# MINIBLDC.net
KiCad netlist of a schematic drawn in Altium Designer
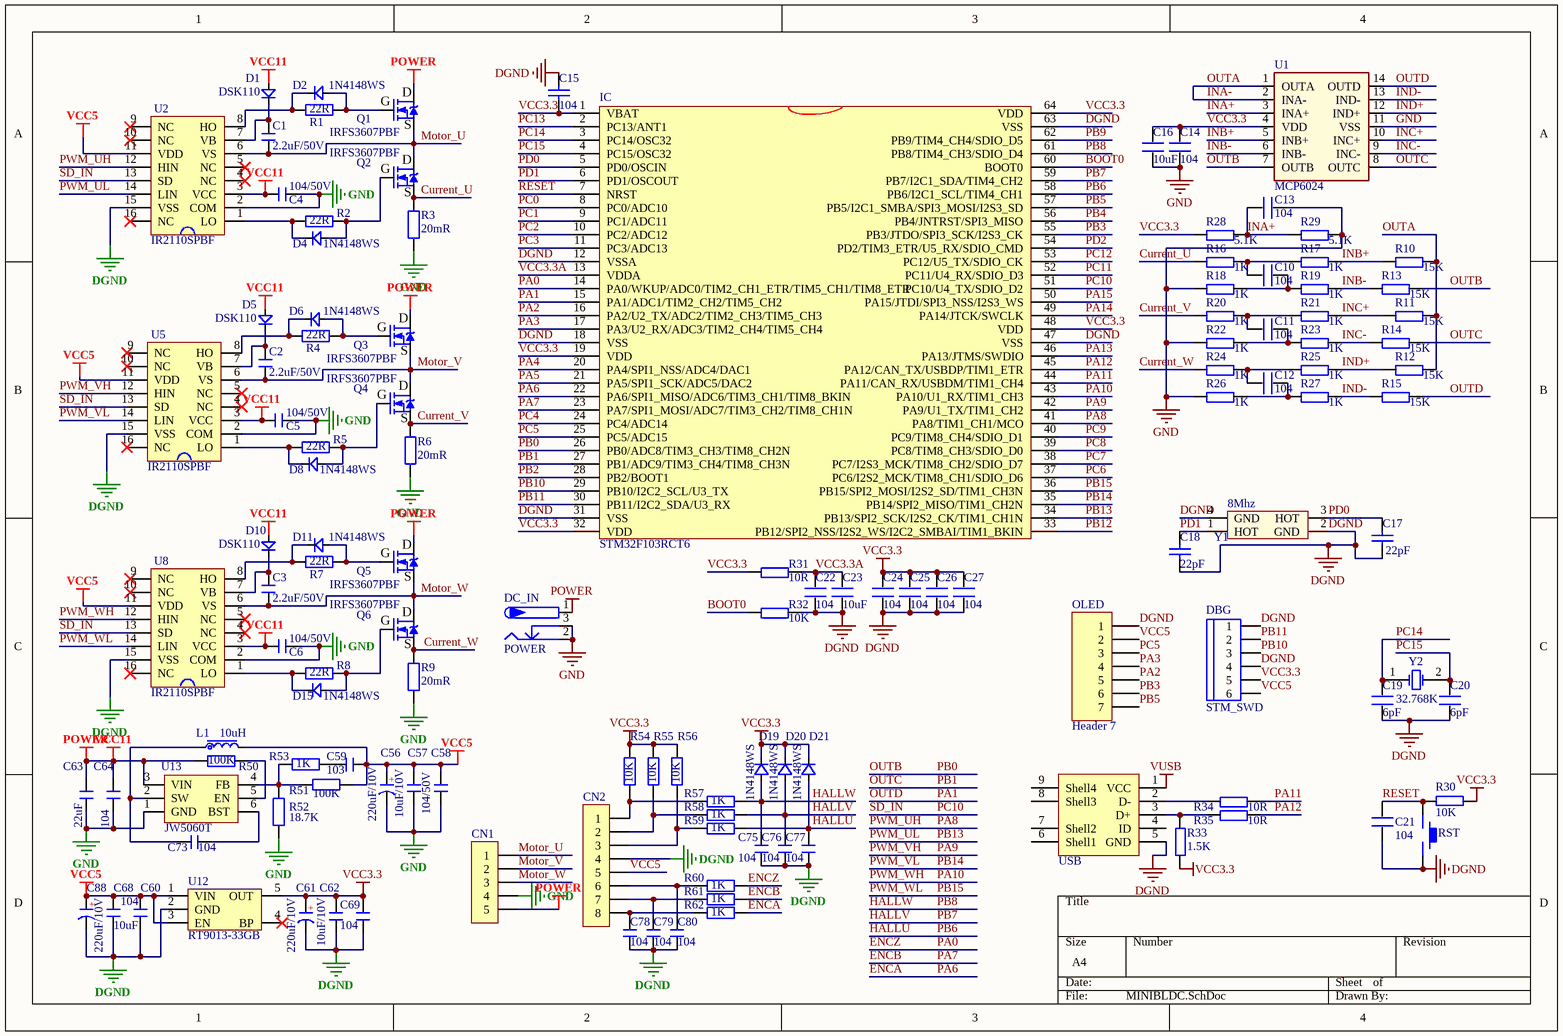
[diagram p0: MINIBLDC.SchDoc]

(export (version "E")
  (design (tool "Eeschema 10.0.6"))
  (components
    (comp (ref "C1")
      (value "2.2uF/50V")
      (footprint "C 0603")
      (description "无极性贴片电容")
      (fields (field (name "版权归属") "源创客"))
      (libsource (lib "电阻-电容-电感") (part "C"))
    )
    (comp (ref "C2")
      (value "2.2uF/50V")
      (footprint "C 0603")
      (description "无极性贴片电容")
      (fields (field (name "版权归属") "源创客"))
      (libsource (lib "电阻-电容-电感") (part "C"))
    )
    (comp (ref "C3")
      (value "2.2uF/50V")
      (footprint "C 0603")
      (description "无极性贴片电容")
      (fields (field (name "版权归属") "源创客"))
      (libsource (lib "电阻-电容-电感") (part "C"))
    )
    (comp (ref "C4")
      (value "104/50V")
      (footprint "C 0603")
      (description "无极性贴片电容")
      (fields (field (name "版权归属") "源创客"))
      (libsource (lib "电阻-电容-电感") (part "C"))
    )
    (comp (ref "C5")
      (value "104/50V")
      (footprint "C 0603")
      (description "无极性贴片电容")
      (fields (field (name "版权归属") "源创客"))
      (libsource (lib "电阻-电容-电感") (part "C"))
    )
    (comp (ref "C6")
      (value "104/50V")
      (footprint "C 0603")
      (description "无极性贴片电容")
      (fields (field (name "版权归属") "源创客"))
      (libsource (lib "电阻-电容-电感") (part "C"))
    )
    (comp (ref "C10") (value "104") (footprint "C 0603") (libsource (lib "IMX6UL_ALPHA(底板)_V2.0") (part "C")))
    (comp (ref "C11") (value "104") (footprint "C 0603") (libsource (lib "IMX6UL_ALPHA(底板)_V2.0") (part "C")))
    (comp (ref "C12") (value "104") (footprint "C 0603") (libsource (lib "IMX6UL_ALPHA(底板)_V2.0") (part "C")))
    (comp (ref "C13") (value "104") (footprint "C 0603") (libsource (lib "IMX6UL_ALPHA(底板)_V2.0") (part "C")))
    (comp (ref "C14") (value "104") (footprint "C 0603") (libsource (lib "IMX6UL_ALPHA(底板)_V2.0") (part "C")))
    (comp (ref "C15") (value "104") (footprint "C 0603") (libsource (lib "L476") (part "CAP")))
    (comp (ref "C16")
      (value "10uF")
      (footprint "C 0603")
      (libsource (lib "IMX6UL_ALPHA(底板)_V2.0") (part "C"))
    )
    (comp (ref "C17") (value "22pF") (footprint "C 0603") (libsource (lib "L476") (part "CAP")))
    (comp (ref "C18") (value "22pF") (footprint "C 0603") (libsource (lib "L476") (part "CAP")))
    (comp (ref "C19")
      (value "6pF")
      (footprint "C 0603")
      (libsource (lib "WarShip V3 STM32103封装库") (part "C"))
    )
    (comp (ref "C20")
      (value "6pF")
      (footprint "C 0603")
      (libsource (lib "WarShip V3 STM32103封装库") (part "C"))
    )
    (comp (ref "C21")
      (value "104")
      (footprint "C 0603")
      (libsource (lib "WarShip V3 STM32103封装库") (part "C"))
    )
    (comp (ref "C22")
      (value "104")
      (footprint "C 0603")
      (libsource (lib "WarShip V3 STM32103封装库") (part "C"))
    )
    (comp (ref "C23")
      (value "10uF")
      (footprint "C 0603")
      (libsource (lib "WarShip V3 STM32103封装库") (part "C"))
    )
    (comp (ref "C24")
      (value "104")
      (footprint "C 0603")
      (libsource (lib "WarShip V3 STM32103封装库") (part "C"))
    )
    (comp (ref "C25")
      (value "104")
      (footprint "C 0603")
      (libsource (lib "WarShip V3 STM32103封装库") (part "C"))
    )
    (comp (ref "C26")
      (value "104")
      (footprint "C 0603")
      (libsource (lib "WarShip V3 STM32103封装库") (part "C"))
    )
    (comp (ref "C27")
      (value "104")
      (footprint "C 0603")
      (libsource (lib "WarShip V3 STM32103封装库") (part "C"))
    )
    (comp (ref "C56")
      (value "220uF/10V")
      (footprint "CM D(6.3*5.4)")
      (description "贴片电解电容")
      (fields (field (name "版权归属") "源创客"))
      (libsource (lib "电阻-电容-电感") (part "C-CM"))
    )
    (comp (ref "C57")
      (value "10uF/10V")
      (footprint "C 0603")
      (description "无极性贴片电容")
      (fields (field (name "版权归属") "源创客"))
      (libsource (lib "电阻-电容-电感") (part "C"))
    )
    (comp (ref "C58")
      (value "104/50V")
      (footprint "C 0603")
      (description "无极性贴片电容")
      (fields (field (name "版权归属") "源创客"))
      (libsource (lib "电阻-电容-电感") (part "C"))
    )
    (comp (ref "C59")
      (value "103")
      (footprint "C 0603")
      (description "无极性贴片电容")
      (fields (field (name "版权归属") "源创客"))
      (libsource (lib "电阻-电容-电感") (part "C"))
    )
    (comp (ref "C60")
      (value "104")
      (footprint "C 0603")
      (description "无极性贴片电容")
      (fields (field (name "版权归属") "源创客"))
      (libsource (lib "电阻-电容-电感") (part "C"))
    )
    (comp (ref "C61")
      (value "220uF/10V")
      (footprint "CM D(6.3*5.4)")
      (description "贴片电解电容")
      (fields (field (name "版权归属") "源创客"))
      (libsource (lib "电阻-电容-电感") (part "C-CM"))
    )
    (comp (ref "C62")
      (value "10uF/10V")
      (footprint "C 0603")
      (description "无极性贴片电容")
      (fields (field (name "版权归属") "源创客"))
      (libsource (lib "电阻-电容-电感") (part "C"))
    )
    (comp (ref "C63")
      (value "22uF")
      (footprint "C 0805")
      (description "无极性贴片电容")
      (fields (field (name "版权归属") "源创客"))
      (libsource (lib "电阻-电容-电感") (part "C"))
    )
    (comp (ref "C64")
      (value "104")
      (footprint "C 0603")
      (description "无极性贴片电容")
      (fields (field (name "版权归属") "源创客"))
      (libsource (lib "电阻-电容-电感") (part "C"))
    )
    (comp (ref "C68")
      (value "10uF")
      (footprint "C 0603")
      (description "无极性贴片电容")
      (fields (field (name "版权归属") "源创客"))
      (libsource (lib "电阻-电容-电感") (part "C"))
    )
    (comp (ref "C69")
      (value "104")
      (footprint "C 0603")
      (description "无极性贴片电容")
      (fields (field (name "版权归属") "源创客"))
      (libsource (lib "电阻-电容-电感") (part "C"))
    )
    (comp (ref "C73")
      (value "104")
      (footprint "C 0603")
      (description "无极性贴片电容")
      (fields (field (name "版权归属") "源创客"))
      (libsource (lib "电阻-电容-电感") (part "C"))
    )
    (comp (ref "C75")
      (value "104")
      (footprint "C 0603")
      (description "无极性贴片电容")
      (fields (field (name "版权归属") "源创客"))
      (libsource (lib "电阻-电容-电感") (part "C"))
    )
    (comp (ref "C76")
      (value "104")
      (footprint "C 0603")
      (description "无极性贴片电容")
      (fields (field (name "版权归属") "源创客"))
      (libsource (lib "电阻-电容-电感") (part "C"))
    )
    (comp (ref "C77")
      (value "104")
      (footprint "C 0603")
      (description "无极性贴片电容")
      (fields (field (name "版权归属") "源创客"))
      (libsource (lib "电阻-电容-电感") (part "C"))
    )
    (comp (ref "C78")
      (value "104")
      (footprint "C 0603")
      (description "无极性贴片电容")
      (fields (field (name "版权归属") "源创客"))
      (libsource (lib "电阻-电容-电感") (part "C"))
    )
    (comp (ref "C79")
      (value "104")
      (footprint "C 0603")
      (description "无极性贴片电容")
      (fields (field (name "版权归属") "源创客"))
      (libsource (lib "电阻-电容-电感") (part "C"))
    )
    (comp (ref "C80")
      (value "104")
      (footprint "C 0603")
      (description "无极性贴片电容")
      (fields (field (name "版权归属") "源创客"))
      (libsource (lib "电阻-电容-电感") (part "C"))
    )
    (comp (ref "C88")
      (value "220uF/10V")
      (footprint "CM D(6.3*5.4)")
      (description "贴片电解电容")
      (fields (field (name "版权归属") "源创客"))
      (libsource (lib "电阻-电容-电感") (part "C-CM"))
    )
    (comp (ref "CN1")
      (value "HDR-1X5")
      (footprint "KF7620-5P")
      (description "5P接插件")
      (fields (field (name "版权归属") "源创客"))
      (libsource (lib "接插件") (part "Header 5"))
    )
    (comp (ref "CN2")
      (value "HDR-1X8")
      (footprint "HDR2.54-LI-8P")
      (description "8P接插件")
      (fields (field (name "版权归属") "源创客"))
      (libsource (lib "接插件") (part "Header 8"))
    )
    (comp (ref "D1")
      (value "DSK110")
      (footprint "SOD-123F")
      (description "通用二极管 100V-1A")
      (fields (field (name "版权归属") "源创客"))
      (libsource (lib "二极管-整流桥") (part "DSK110"))
    )
    (comp (ref "D2")
      (value "1N4148WS")
      (footprint "SOD-323")
      (description "通用二极管 700V-1A")
      (fields (field (name "版权归属") "源创客"))
      (libsource (lib "二极管-整流桥") (part "FR107"))
    )
    (comp (ref "D4")
      (value "1N4148WS")
      (footprint "SOD-323")
      (description "通用二极管 700V-1A")
      (fields (field (name "版权归属") "源创客"))
      (libsource (lib "二极管-整流桥") (part "FR107"))
    )
    (comp (ref "D5")
      (value "DSK110")
      (footprint "SOD-123F")
      (description "通用二极管 100V-1A")
      (fields (field (name "版权归属") "源创客"))
      (libsource (lib "二极管-整流桥") (part "DSK110"))
    )
    (comp (ref "D6")
      (value "1N4148WS")
      (footprint "SOD-323")
      (description "通用二极管 700V-1A")
      (fields (field (name "版权归属") "源创客"))
      (libsource (lib "二极管-整流桥") (part "FR107"))
    )
    (comp (ref "D8")
      (value "1N4148WS")
      (footprint "SOD-323")
      (description "通用二极管 700V-1A")
      (fields (field (name "版权归属") "源创客"))
      (libsource (lib "二极管-整流桥") (part "FR107"))
    )
    (comp (ref "D10")
      (value "DSK110")
      (footprint "SOD-123F")
      (description "通用二极管 100V-1A")
      (fields (field (name "版权归属") "源创客"))
      (libsource (lib "二极管-整流桥") (part "DSK110"))
    )
    (comp (ref "D11")
      (value "1N4148WS")
      (footprint "SOD-323")
      (description "通用二极管 700V-1A")
      (fields (field (name "版权归属") "源创客"))
      (libsource (lib "二极管-整流桥") (part "FR107"))
    )
    (comp (ref "D15")
      (value "1N4148WS")
      (footprint "SOD-323")
      (description "通用二极管 700V-1A")
      (fields (field (name "版权归属") "源创客"))
      (libsource (lib "二极管-整流桥") (part "FR107"))
    )
    (comp (ref "D19")
      (value "1N4148WS")
      (footprint "SOD-323")
      (description "通用二极管 1000V-1A")
      (fields (field (name "版权归属") "源创客"))
      (libsource (lib "二极管-整流桥") (part "RS1M"))
    )
    (comp (ref "D20")
      (value "1N4148WS")
      (footprint "SOD-323")
      (description "通用二极管 1000V-1A")
      (fields (field (name "版权归属") "源创客"))
      (libsource (lib "二极管-整流桥") (part "RS1M"))
    )
    (comp (ref "D21")
      (value "1N4148WS")
      (footprint "SOD-323")
      (description "通用二极管 1000V-1A")
      (fields (field (name "版权归属") "源创客"))
      (libsource (lib "二极管-整流桥") (part "RS1M"))
    )
    (comp (ref "DBG") (value "STM_SWD") (footprint "SH1.0-6P") (libsource (lib "MiniFly ") (part "HEAD6")))
    (comp (ref "DC_IN")
      (value "POWER")
      (footprint "DC10B")
      (description "低压电源接口")
      (fields (field (name "版权归属") "源创客"))
      (libsource (lib "IMX6UL_ALPHA(底板)_V2.0") (part "P-DC"))
    )
    (comp (ref "IC")
      (value "STM32F103RCT6")
      (footprint "LQFP64-10*10")
      (libsource (lib "MiniSTM32 V3.0封装库") (part "STM32F103RDT6"))
    )
    (comp (ref "L1")
      (value "10uH")
      (footprint "L-SMD-0420")
      (description "功率屏蔽电感")
      (fields (field (name "版权归属") "源创客"))
      (libsource (lib "电阻-电容-电感") (part "L-CDRH"))
    )
    (comp (ref "OLED")
      (value "Header 7")
      (footprint "HDR2.54-M-LI-7P")
      (description "Header, 7-Pin")
      (fields (field (name "PUBLISHER") "Altium Limited"))
      (libsource (lib "Miscellaneous Connectors") (part "Header 7"))
    )
    (comp (ref "Q1")
      (value "IRFS3607PBF")
      (footprint "TO263-3B")
      (description "NMOS 75V+80A 7.4mΩ")
      (fields (field (name "版权归属") "源创客"))
      (libsource (lib "场效应管-可控硅") (part "IRFS3607PBF"))
    )
    (comp (ref "Q2")
      (value "IRFS3607PBF")
      (footprint "TO263-3B")
      (description "NMOS 75V+80A 7.4mΩ")
      (fields (field (name "版权归属") "源创客"))
      (libsource (lib "场效应管-可控硅") (part "IRFS3607PBF"))
    )
    (comp (ref "Q3")
      (value "IRFS3607PBF")
      (footprint "TO263-3B")
      (description "NMOS 75V+80A 7.4mΩ")
      (fields (field (name "版权归属") "源创客"))
      (libsource (lib "场效应管-可控硅") (part "IRFS3607PBF"))
    )
    (comp (ref "Q4")
      (value "IRFS3607PBF")
      (footprint "TO263-3B")
      (description "NMOS 75V+80A 7.4mΩ")
      (fields (field (name "版权归属") "源创客"))
      (libsource (lib "场效应管-可控硅") (part "IRFS3607PBF"))
    )
    (comp (ref "Q5")
      (value "IRFS3607PBF")
      (footprint "TO263-3B")
      (description "NMOS 75V+80A 7.4mΩ")
      (fields (field (name "版权归属") "源创客"))
      (libsource (lib "场效应管-可控硅") (part "IRFS3607PBF"))
    )
    (comp (ref "Q6")
      (value "IRFS3607PBF")
      (footprint "TO263-3B")
      (description "NMOS 75V+80A 7.4mΩ")
      (fields (field (name "版权归属") "源创客"))
      (libsource (lib "场效应管-可控硅") (part "IRFS3607PBF"))
    )
    (comp (ref "R1")
      (value "22R")
      (footprint "R 0603")
      (description "贴片电阻")
      (fields (field (name "版权归属") "源创客"))
      (libsource (lib "电阻-电容-电感") (part "R"))
    )
    (comp (ref "R2")
      (value "22R")
      (footprint "R 0603")
      (description "贴片电阻")
      (fields (field (name "版权归属") "源创客"))
      (libsource (lib "电阻-电容-电感") (part "R"))
    )
    (comp (ref "R3")
      (value "20mR")
      (footprint "R 2512_L")
      (description "贴片电阻")
      (fields (field (name "版权归属") "源创客"))
      (libsource (lib "电阻-电容-电感") (part "R"))
    )
    (comp (ref "R4")
      (value "22R")
      (footprint "R 0603")
      (description "贴片电阻")
      (fields (field (name "版权归属") "源创客"))
      (libsource (lib "电阻-电容-电感") (part "R"))
    )
    (comp (ref "R5")
      (value "22R")
      (footprint "R 0603")
      (description "贴片电阻")
      (fields (field (name "版权归属") "源创客"))
      (libsource (lib "电阻-电容-电感") (part "R"))
    )
    (comp (ref "R6")
      (value "20mR")
      (footprint "R 2512_L")
      (description "贴片电阻")
      (fields (field (name "版权归属") "源创客"))
      (libsource (lib "电阻-电容-电感") (part "R"))
    )
    (comp (ref "R7")
      (value "22R")
      (footprint "R 0603")
      (description "贴片电阻")
      (fields (field (name "版权归属") "源创客"))
      (libsource (lib "电阻-电容-电感") (part "R"))
    )
    (comp (ref "R8")
      (value "22R")
      (footprint "R 0603")
      (description "贴片电阻")
      (fields (field (name "版权归属") "源创客"))
      (libsource (lib "电阻-电容-电感") (part "R"))
    )
    (comp (ref "R9")
      (value "20mR")
      (footprint "R 2512_L")
      (description "贴片电阻")
      (fields (field (name "版权归属") "源创客"))
      (libsource (lib "电阻-电容-电感") (part "R"))
    )
    (comp (ref "R10") (value "15K") (footprint "R 0603") (libsource (lib "IMX6UL_ALPHA(底板)_V2.0") (part "R")))
    (comp (ref "R11") (value "15K") (footprint "R 0603") (libsource (lib "IMX6UL_ALPHA(底板)_V2.0") (part "R")))
    (comp (ref "R12") (value "15K") (footprint "R 0603") (libsource (lib "IMX6UL_ALPHA(底板)_V2.0") (part "R")))
    (comp (ref "R13") (value "15K") (footprint "R 0603") (libsource (lib "IMX6UL_ALPHA(底板)_V2.0") (part "R")))
    (comp (ref "R14") (value "15K") (footprint "R 0603") (libsource (lib "IMX6UL_ALPHA(底板)_V2.0") (part "R")))
    (comp (ref "R15") (value "15K") (footprint "R 0603") (libsource (lib "IMX6UL_ALPHA(底板)_V2.0") (part "R")))
    (comp (ref "R16") (value "1K") (footprint "R 0603") (libsource (lib "IMX6UL_ALPHA(底板)_V2.0") (part "R")))
    (comp (ref "R17") (value "1K") (footprint "R 0603") (libsource (lib "IMX6UL_ALPHA(底板)_V2.0") (part "R")))
    (comp (ref "R18") (value "1K") (footprint "R 0603") (libsource (lib "IMX6UL_ALPHA(底板)_V2.0") (part "R")))
    (comp (ref "R19") (value "1K") (footprint "R 0603") (libsource (lib "IMX6UL_ALPHA(底板)_V2.0") (part "R")))
    (comp (ref "R20") (value "1K") (footprint "R 0603") (libsource (lib "IMX6UL_ALPHA(底板)_V2.0") (part "R")))
    (comp (ref "R21") (value "1K") (footprint "R 0603") (libsource (lib "IMX6UL_ALPHA(底板)_V2.0") (part "R")))
    (comp (ref "R22") (value "1K") (footprint "R 0603") (libsource (lib "IMX6UL_ALPHA(底板)_V2.0") (part "R")))
    (comp (ref "R23") (value "1K") (footprint "R 0603") (libsource (lib "IMX6UL_ALPHA(底板)_V2.0") (part "R")))
    (comp (ref "R24") (value "1K") (footprint "R 0603") (libsource (lib "IMX6UL_ALPHA(底板)_V2.0") (part "R")))
    (comp (ref "R25") (value "1K") (footprint "R 0603") (libsource (lib "IMX6UL_ALPHA(底板)_V2.0") (part "R")))
    (comp (ref "R26") (value "1K") (footprint "R 0603") (libsource (lib "IMX6UL_ALPHA(底板)_V2.0") (part "R")))
    (comp (ref "R27") (value "1K") (footprint "R 0603") (libsource (lib "IMX6UL_ALPHA(底板)_V2.0") (part "R")))
    (comp (ref "R28")
      (value "5.1K")
      (footprint "R 0603")
      (libsource (lib "IMX6UL_ALPHA(底板)_V2.0") (part "R"))
    )
    (comp (ref "R29")
      (value "5.1K")
      (footprint "R 0603")
      (libsource (lib "IMX6UL_ALPHA(底板)_V2.0") (part "R"))
    )
    (comp (ref "R30")
      (value "10K")
      (footprint "R 0603")
      (libsource (lib "WarShip V3 STM32103封装库") (part "R"))
    )
    (comp (ref "R31")
      (value "10R")
      (footprint "R 0603")
      (libsource (lib "WarShip V3 STM32103封装库") (part "R"))
    )
    (comp (ref "R32")
      (value "10K")
      (footprint "R 0603")
      (libsource (lib "WarShip V3 STM32103封装库") (part "R"))
    )
    (comp (ref "R33")
      (value "1.5K")
      (footprint "R 0603")
      (libsource (lib "WarShip V3 STM32103封装库") (part "R"))
    )
    (comp (ref "R34")
      (value "10R")
      (footprint "R 0603")
      (libsource (lib "WarShip V3 STM32103封装库") (part "R"))
    )
    (comp (ref "R35")
      (value "10R")
      (footprint "R 0603")
      (libsource (lib "WarShip V3 STM32103封装库") (part "R"))
    )
    (comp (ref "R50")
      (value "100K")
      (footprint "R 0603")
      (description "贴片电阻")
      (fields (field (name "版权归属") "源创客"))
      (libsource (lib "电阻-电容-电感") (part "R"))
    )
    (comp (ref "R51")
      (value "100K")
      (footprint "R 0603")
      (description "贴片电阻")
      (fields (field (name "版权归属") "源创客"))
      (libsource (lib "电阻-电容-电感") (part "R"))
    )
    (comp (ref "R52")
      (value "18.7K")
      (footprint "R 0603")
      (description "贴片电阻")
      (fields (field (name "版权归属") "源创客"))
      (libsource (lib "电阻-电容-电感") (part "R"))
    )
    (comp (ref "R53")
      (value "1K")
      (footprint "R 0603")
      (description "贴片电阻")
      (fields (field (name "版权归属") "源创客"))
      (libsource (lib "电阻-电容-电感") (part "R"))
    )
    (comp (ref "R54")
      (value "10K")
      (footprint "R 0603")
      (description "贴片电阻")
      (fields (field (name "版权归属") "源创客"))
      (libsource (lib "电阻-电容-电感") (part "R"))
    )
    (comp (ref "R55")
      (value "10K")
      (footprint "R 0603")
      (description "贴片电阻")
      (fields (field (name "版权归属") "源创客"))
      (libsource (lib "电阻-电容-电感") (part "R"))
    )
    (comp (ref "R56")
      (value "10K")
      (footprint "R 0603")
      (description "贴片电阻")
      (fields (field (name "版权归属") "源创客"))
      (libsource (lib "电阻-电容-电感") (part "R"))
    )
    (comp (ref "R57")
      (value "1K")
      (footprint "R 0603")
      (description "贴片电阻")
      (fields (field (name "版权归属") "源创客"))
      (libsource (lib "电阻-电容-电感") (part "R"))
    )
    (comp (ref "R58")
      (value "1K")
      (footprint "R 0603")
      (description "贴片电阻")
      (fields (field (name "版权归属") "源创客"))
      (libsource (lib "电阻-电容-电感") (part "R"))
    )
    (comp (ref "R59")
      (value "1K")
      (footprint "R 0603")
      (description "贴片电阻")
      (fields (field (name "版权归属") "源创客"))
      (libsource (lib "电阻-电容-电感") (part "R"))
    )
    (comp (ref "R60")
      (value "1K")
      (footprint "R 0603")
      (description "贴片电阻")
      (fields (field (name "版权归属") "源创客"))
      (libsource (lib "电阻-电容-电感") (part "R"))
    )
    (comp (ref "R61")
      (value "1K")
      (footprint "R 0603")
      (description "贴片电阻")
      (fields (field (name "版权归属") "源创客"))
      (libsource (lib "电阻-电容-电感") (part "R"))
    )
    (comp (ref "R62")
      (value "1K")
      (footprint "R 0603")
      (description "贴片电阻")
      (fields (field (name "版权归属") "源创客"))
      (libsource (lib "电阻-电容-电感") (part "R"))
    )
    (comp (ref "RST")
      (value "KEY-SMD")
      (footprint "TSW SMD-3*6*2.5")
      (description "KEY,SMD,324225")
      (libsource (lib "Pandora_STM32L4_Board_V2.4") (part "S-KEY-SMD-324225"))
    )
    (comp (ref "U1") (value "MCP6024") (footprint "SOP14_L") (libsource (lib "MINIBLDC") (part "MCP6024")))
    (comp (ref "U2")
      (value "IR2110SPBF")
      (footprint "SOP16W_L")
      (description "半桥驱动 500V,10-20V  Ton/off=120ns&94ns MT=10nS")
      (libsource (lib "IC芯片") (part "IR2110SPBF"))
    )
    (comp (ref "U5")
      (value "IR2110SPBF")
      (footprint "SOP16W_L")
      (description "半桥驱动 500V,10-20V  Ton/off=120ns&94ns MT=10nS")
      (libsource (lib "IC芯片") (part "IR2110SPBF"))
    )
    (comp (ref "U8")
      (value "IR2110SPBF")
      (footprint "SOP16W_L")
      (description "半桥驱动 500V,10-20V  Ton/off=120ns&94ns MT=10nS")
      (libsource (lib "IC芯片") (part "IR2110SPBF"))
    )
    (comp (ref "U12")
      (value "RT9013-33GB")
      (footprint "SOT23-5N")
      (description "LDO")
      (fields (field (name "版权归属") "源创客"))
      (libsource (lib "LDO和DCDC") (part "LDO RT9193"))
    )
    (comp (ref "U13")
      (value "JW5060T")
      (footprint "SOT23-6L")
      (description "DC降压芯片")
      (libsource (lib "LDO和DCDC") (part "DC JW5060T_6"))
    )
    (comp (ref "USB")
      (value "MICRO-USB")
      (footprint "USB-AB-5S")
      (description "Micro USB 5.9有柱脚长1.25加长针")
      (libsource (lib "Pandora_STM32L4_Board_V2.4") (part "J-MICRO-USB-5S"))
    )
    (comp (ref "Y1")
      (value "8Mhz")
      (footprint "XTAL-3225")
      (description "3225贴片无源晶振")
      (libsource (lib "ALIENTEK_COMPONENT") (part "XTAL_3225"))
    )
    (comp (ref "Y2")
      (value "32.768K")
      (footprint "OSC 3215-2P")
      (description "Crystal Oscillator")
      (fields (field (name "PUBLISHER") "Altium Limited"))
      (libsource (lib "WarShip V3 STM32103封装库") (part "XTAL"))
    )
  )
  (nets
    (net (code "1") (name "/BOOT0") (class "Default")
      (node (ref "IC") (pin "60") (pinfunction "BOOT0_60") (pintype "passive"))
      (node (ref "R32") (pin "1") (pintype "passive"))
    )
    (net (code "2") (name "/Current_U") (class "Default")
      (node (ref "Q2") (pin "3") (pinfunction "S_3") (pintype "passive"))
      (node (ref "R16") (pin "1") (pintype "passive"))
      (node (ref "R3") (pin "2") (pinfunction "2_2") (pintype "passive"))
    )
    (net (code "3") (name "/Current_V") (class "Default")
      (node (ref "Q4") (pin "3") (pinfunction "S_3") (pintype "passive"))
      (node (ref "R20") (pin "1") (pintype "passive"))
      (node (ref "R6") (pin "2") (pinfunction "2_2") (pintype "passive"))
    )
    (net (code "4") (name "/Current_W") (class "Default")
      (node (ref "Q6") (pin "3") (pinfunction "S_3") (pintype "passive"))
      (node (ref "R24") (pin "1") (pintype "passive"))
      (node (ref "R9") (pin "2") (pinfunction "2_2") (pintype "passive"))
    )
    (net (code "5") (name "/ENCA") (class "Default")
      (node (ref "IC") (pin "22") (pinfunction "PA6/SPI1_MISO/ADC6/TIM3_CH1/TIM8_BKIN_22") (pintype "passive"))
      (node (ref "R62") (pin "2") (pinfunction "2_2") (pintype "passive"))
    )
    (net (code "6") (name "/ENCB") (class "Default")
      (node (ref "IC") (pin "23") (pinfunction "PA7/SPI1_MOSI/ADC7/TIM3_CH2/TIM8_CH1N_23") (pintype "passive"))
      (node (ref "R61") (pin "2") (pinfunction "2_2") (pintype "passive"))
    )
    (net (code "7") (name "/ENCZ") (class "Default")
      (node (ref "IC") (pin "14") (pinfunction "PA0/WKUP/ADC0/TIM2_CH1_ETR/TIM5_CH1/TIM8_ETR_14") (pintype "passive"))
      (node (ref "R60") (pin "2") (pinfunction "2_2") (pintype "passive"))
    )
    (net (code "8") (name "/HALLU") (class "Default")
      (node (ref "C77") (pin "1") (pinfunction "1_1") (pintype "passive"))
      (node (ref "D21") (pin "1") (pinfunction "A_1") (pintype "passive"))
      (node (ref "IC") (pin "58") (pinfunction "PB6/I2C1_SCL/TIM4_CH1_58") (pintype "passive"))
      (node (ref "R59") (pin "2") (pinfunction "2_2") (pintype "passive"))
    )
    (net (code "9") (name "/HALLV") (class "Default")
      (node (ref "C76") (pin "1") (pinfunction "1_1") (pintype "passive"))
      (node (ref "D20") (pin "1") (pinfunction "A_1") (pintype "passive"))
      (node (ref "IC") (pin "59") (pinfunction "PB7/I2C1_SDA/TIM4_CH2_59") (pintype "passive"))
      (node (ref "R58") (pin "2") (pinfunction "2_2") (pintype "passive"))
    )
    (net (code "10") (name "/HALLW") (class "Default")
      (node (ref "C75") (pin "1") (pinfunction "1_1") (pintype "passive"))
      (node (ref "D19") (pin "1") (pinfunction "A_1") (pintype "passive"))
      (node (ref "IC") (pin "61") (pinfunction "PB8/TIM4_CH3/SDIO_D4_61") (pintype "passive"))
      (node (ref "R57") (pin "2") (pinfunction "2_2") (pintype "passive"))
    )
    (net (code "11") (name "/INA+") (class "Default")
      (node (ref "C13") (pin "1") (pintype "passive"))
      (node (ref "R28") (pin "2") (pintype "passive"))
      (node (ref "R29") (pin "1") (pintype "passive"))
      (node (ref "U1") (pin "3") (pinfunction "INA+_3") (pintype "passive"))
    )
    (net (code "12") (name "/INA-") (class "Default")
      (node (ref "R10") (pin "2") (pintype "passive"))
      (node (ref "R11") (pin "2") (pintype "passive"))
      (node (ref "R12") (pin "2") (pintype "passive"))
      (node (ref "U1") (pin "1") (pinfunction "OUTA_1") (pintype "passive"))
      (node (ref "U1") (pin "2") (pinfunction "INA-_2") (pintype "passive"))
    )
    (net (code "13") (name "/INB+") (class "Default")
      (node (ref "R10") (pin "1") (pintype "passive"))
      (node (ref "R17") (pin "2") (pintype "passive"))
      (node (ref "U1") (pin "5") (pinfunction "INB+_5") (pintype "passive"))
    )
    (net (code "14") (name "/INB-") (class "Default")
      (node (ref "R13") (pin "1") (pintype "passive"))
      (node (ref "R19") (pin "2") (pintype "passive"))
      (node (ref "U1") (pin "6") (pinfunction "INB-_6") (pintype "passive"))
    )
    (net (code "15") (name "/INC+") (class "Default")
      (node (ref "R11") (pin "1") (pintype "passive"))
      (node (ref "R21") (pin "2") (pintype "passive"))
      (node (ref "U1") (pin "10") (pinfunction "INC+_10") (pintype "passive"))
    )
    (net (code "16") (name "/INC-") (class "Default")
      (node (ref "R14") (pin "1") (pintype "passive"))
      (node (ref "R23") (pin "2") (pintype "passive"))
      (node (ref "U1") (pin "9") (pinfunction "INC-_9") (pintype "passive"))
    )
    (net (code "17") (name "/IND+") (class "Default")
      (node (ref "R12") (pin "1") (pintype "passive"))
      (node (ref "R25") (pin "2") (pintype "passive"))
      (node (ref "U1") (pin "12") (pinfunction "IND+_12") (pintype "passive"))
    )
    (net (code "18") (name "/IND-") (class "Default")
      (node (ref "R15") (pin "1") (pintype "passive"))
      (node (ref "R27") (pin "2") (pintype "passive"))
      (node (ref "U1") (pin "13") (pinfunction "IND-_13") (pintype "passive"))
    )
    (net (code "19") (name "/Motor_U") (class "Default")
      (node (ref "C1") (pin "1") (pinfunction "1_1") (pintype "passive"))
      (node (ref "CN1") (pin "1") (pinfunction "1_1") (pintype "passive"))
      (node (ref "Q1") (pin "3") (pinfunction "S_3") (pintype "passive"))
      (node (ref "Q2") (pin "2") (pinfunction "D_2") (pintype "passive"))
      (node (ref "U2") (pin "6") (pinfunction "VS_6") (pintype "passive"))
    )
    (net (code "20") (name "/Motor_V") (class "Default")
      (node (ref "C2") (pin "1") (pinfunction "1_1") (pintype "passive"))
      (node (ref "CN1") (pin "2") (pinfunction "2_2") (pintype "passive"))
      (node (ref "Q3") (pin "3") (pinfunction "S_3") (pintype "passive"))
      (node (ref "Q4") (pin "2") (pinfunction "D_2") (pintype "passive"))
      (node (ref "U5") (pin "6") (pinfunction "VS_6") (pintype "passive"))
    )
    (net (code "21") (name "/Motor_W") (class "Default")
      (node (ref "C3") (pin "1") (pinfunction "1_1") (pintype "passive"))
      (node (ref "CN1") (pin "3") (pinfunction "3_3") (pintype "passive"))
      (node (ref "Q5") (pin "3") (pinfunction "S_3") (pintype "passive"))
      (node (ref "Q6") (pin "2") (pinfunction "D_2") (pintype "passive"))
      (node (ref "U8") (pin "6") (pinfunction "VS_6") (pintype "passive"))
    )
    (net (code "22") (name "/OUTB") (class "Default")
      (node (ref "IC") (pin "26") (pinfunction "PB0/ADC8/TIM3_CH3/TIM8_CH2N_26") (pintype "passive"))
      (node (ref "R13") (pin "2") (pintype "passive"))
      (node (ref "U1") (pin "7") (pinfunction "OUTB_7") (pintype "passive"))
    )
    (net (code "23") (name "/OUTC") (class "Default")
      (node (ref "IC") (pin "27") (pinfunction "PB1/ADC9/TIM3_CH4/TIM8_CH3N_27") (pintype "passive"))
      (node (ref "R14") (pin "2") (pintype "passive"))
      (node (ref "U1") (pin "8") (pinfunction "OUTC_8") (pintype "passive"))
    )
    (net (code "24") (name "/OUTD") (class "Default")
      (node (ref "IC") (pin "15") (pinfunction "PA1/ADC1/TIM2_CH2/TIM5_CH2_15") (pintype "passive"))
      (node (ref "R15") (pin "2") (pintype "passive"))
      (node (ref "U1") (pin "14") (pinfunction "OUTD_14") (pintype "passive"))
    )
    (net (code "25") (name "/PA2") (class "Default")
      (node (ref "IC") (pin "16") (pinfunction "PA2/U2_TX/ADC2/TIM2_CH3/TIM5_CH3_16") (pintype "passive"))
      (node (ref "OLED") (pin "5") (pinfunction "5_5") (pintype "passive"))
    )
    (net (code "26") (name "/PA3") (class "Default")
      (node (ref "IC") (pin "17") (pinfunction "PA3/U2_RX/ADC3/TIM2_CH4/TIM5_CH4_17") (pintype "passive"))
      (node (ref "OLED") (pin "4") (pinfunction "4_4") (pintype "passive"))
    )
    (net (code "27") (name "/PA4") (class "Default")
      (node (ref "IC") (pin "20") (pinfunction "PA4/SPI1_NSS/ADC4/DAC1_20") (pintype "passive"))
    )
    (net (code "28") (name "/PA5") (class "Default")
      (node (ref "IC") (pin "21") (pinfunction "PA5/SPI1_SCK/ADC5/DAC2_21") (pintype "passive"))
    )
    (net (code "29") (name "/PA8") (class "Default")
      (node (ref "IC") (pin "41") (pinfunction "PA8/TIM1_CH1/MCO_41") (pintype "passive"))
      (node (ref "U2") (pin "12") (pinfunction "HIN_12") (pintype "passive"))
    )
    (net (code "30") (name "/PA9") (class "Default")
      (node (ref "IC") (pin "42") (pinfunction "PA9/U1_TX/TIM1_CH2_42") (pintype "passive"))
      (node (ref "U5") (pin "12") (pinfunction "HIN_12") (pintype "passive"))
    )
    (net (code "31") (name "/PA10") (class "Default")
      (node (ref "IC") (pin "43") (pinfunction "PA10/U1_RX/TIM1_CH3_43") (pintype "passive"))
      (node (ref "U8") (pin "12") (pinfunction "HIN_12") (pintype "passive"))
    )
    (net (code "32") (name "/PA11") (class "Default")
      (node (ref "IC") (pin "44") (pinfunction "PA11/CAN_RX/USBDM/TIM1_CH4_44") (pintype "passive"))
      (node (ref "R34") (pin "2") (pintype "passive"))
    )
    (net (code "33") (name "/PA12") (class "Default")
      (node (ref "IC") (pin "45") (pinfunction "PA12/CAN_TX/USBDP/TIM1_ETR_45") (pintype "passive"))
      (node (ref "R35") (pin "2") (pintype "passive"))
    )
    (net (code "34") (name "/PA13") (class "Default")
      (node (ref "IC") (pin "46") (pinfunction "PA13/JTMS/SWDIO_46") (pintype "passive"))
    )
    (net (code "35") (name "/PA14") (class "Default")
      (node (ref "IC") (pin "49") (pinfunction "PA14/JTCK/SWCLK_49") (pintype "passive"))
    )
    (net (code "36") (name "/PA15") (class "Default")
      (node (ref "IC") (pin "50") (pinfunction "PA15/JTDI/SPI3_NSS/I2S3_WS_50") (pintype "passive"))
    )
    (net (code "37") (name "/PB2") (class "Default")
      (node (ref "IC") (pin "28") (pinfunction "PB2/BOOT1_28") (pintype "passive"))
    )
    (net (code "38") (name "/PB3") (class "Default")
      (node (ref "IC") (pin "55") (pinfunction "PB3/JTDO/SPI3_SCK/I2S3_CK_55") (pintype "passive"))
      (node (ref "OLED") (pin "6") (pinfunction "6_6") (pintype "passive"))
    )
    (net (code "39") (name "/PB4") (class "Default")
      (node (ref "IC") (pin "56") (pinfunction "PB4/JNTRST/SPI3_MISO_56") (pintype "passive"))
    )
    (net (code "40") (name "/PB5") (class "Default")
      (node (ref "IC") (pin "57") (pinfunction "PB5/I2C1_SMBA/SPI3_MOSI/I2S3_SD_57") (pintype "passive"))
      (node (ref "OLED") (pin "7") (pinfunction "7_7") (pintype "passive"))
    )
    (net (code "41") (name "/PB9") (class "Default")
      (node (ref "IC") (pin "62") (pinfunction "PB9/TIM4_CH4/SDIO_D5_62") (pintype "passive"))
    )
    (net (code "42") (name "/PB10") (class "Default")
      (node (ref "DBG") (pin "3") (pinfunction "3_3") (pintype "passive"))
      (node (ref "IC") (pin "29") (pinfunction "PB10/I2C2_SCL/U3_TX_29") (pintype "passive"))
    )
    (net (code "43") (name "/PB11") (class "Default")
      (node (ref "DBG") (pin "2") (pinfunction "2_2") (pintype "passive"))
      (node (ref "IC") (pin "30") (pinfunction "PB11/I2C2_SDA/U3_RX_30") (pintype "passive"))
    )
    (net (code "44") (name "/PB12") (class "Default")
      (node (ref "IC") (pin "33") (pinfunction "PB12/SPI2_NSS/I2S2_WS/I2C2_SMBAI/TIM1_BKIN_33") (pintype "passive"))
    )
    (net (code "45") (name "/PB13") (class "Default")
      (node (ref "IC") (pin "34") (pinfunction "PB13/SPI2_SCK/I2S2_CK/TIM1_CH1N_34") (pintype "passive"))
      (node (ref "U2") (pin "14") (pinfunction "LIN_14") (pintype "passive"))
    )
    (net (code "46") (name "/PB14") (class "Default")
      (node (ref "IC") (pin "35") (pinfunction "PB14/SPI2_MISO/TIM1_CH2N_35") (pintype "passive"))
      (node (ref "U5") (pin "14") (pinfunction "LIN_14") (pintype "passive"))
    )
    (net (code "47") (name "/PB15") (class "Default")
      (node (ref "IC") (pin "36") (pinfunction "PB15/SPI2_MOSI/I2S2_SD/TIM1_CH3N_36") (pintype "passive"))
      (node (ref "U8") (pin "14") (pinfunction "LIN_14") (pintype "passive"))
    )
    (net (code "48") (name "/PC0") (class "Default")
      (node (ref "IC") (pin "8") (pinfunction "PC0/ADC10_8") (pintype "passive"))
    )
    (net (code "49") (name "/PC1") (class "Default")
      (node (ref "IC") (pin "9") (pinfunction "PC1/ADC11_9") (pintype "passive"))
    )
    (net (code "50") (name "/PC2") (class "Default")
      (node (ref "IC") (pin "10") (pinfunction "PC2/ADC12_10") (pintype "passive"))
    )
    (net (code "51") (name "/PC3") (class "Default")
      (node (ref "IC") (pin "11") (pinfunction "PC3/ADC13_11") (pintype "passive"))
    )
    (net (code "52") (name "/PC4") (class "Default")
      (node (ref "IC") (pin "24") (pinfunction "PC4/ADC14_24") (pintype "passive"))
    )
    (net (code "53") (name "/PC5") (class "Default")
      (node (ref "IC") (pin "25") (pinfunction "PC5/ADC15_25") (pintype "passive"))
      (node (ref "OLED") (pin "3") (pinfunction "3_3") (pintype "passive"))
    )
    (net (code "54") (name "/PC6") (class "Default")
      (node (ref "IC") (pin "37") (pinfunction "PC6/I2S2_MCK/TIM8_CH1/SDIO_D6_37") (pintype "passive"))
    )
    (net (code "55") (name "/PC7") (class "Default")
      (node (ref "IC") (pin "38") (pinfunction "PC7/I2S3_MCK/TIM8_CH2/SDIO_D7_38") (pintype "passive"))
    )
    (net (code "56") (name "/PC8") (class "Default")
      (node (ref "IC") (pin "39") (pinfunction "PC8/TIM8_CH3/SDIO_D0_39") (pintype "passive"))
    )
    (net (code "57") (name "/PC9") (class "Default")
      (node (ref "IC") (pin "40") (pinfunction "PC9/TIM8_CH4/SDIO_D1_40") (pintype "passive"))
    )
    (net (code "58") (name "/PC10") (class "Default")
      (node (ref "IC") (pin "51") (pinfunction "PC10/U4_TX/SDIO_D2_51") (pintype "passive"))
      (node (ref "U2") (pin "13") (pinfunction "SD_13") (pintype "passive"))
      (node (ref "U5") (pin "13") (pinfunction "SD_13") (pintype "passive"))
      (node (ref "U8") (pin "13") (pinfunction "SD_13") (pintype "passive"))
    )
    (net (code "59") (name "/PC11") (class "Default")
      (node (ref "IC") (pin "52") (pinfunction "PC11/U4_RX/SDIO_D3_52") (pintype "passive"))
    )
    (net (code "60") (name "/PC12") (class "Default")
      (node (ref "IC") (pin "53") (pinfunction "PC12/U5_TX/SDIO_CK_53") (pintype "passive"))
    )
    (net (code "61") (name "/PC13") (class "Default")
      (node (ref "IC") (pin "2") (pinfunction "PC13/ANT1_2") (pintype "passive"))
    )
    (net (code "62") (name "/PC14") (class "Default")
      (node (ref "C19") (pin "2") (pintype "passive"))
      (node (ref "IC") (pin "3") (pinfunction "PC14/OSC32_3") (pintype "passive"))
      (node (ref "Y2") (pin "1") (pinfunction "OSC1_1") (pintype "passive"))
    )
    (net (code "63") (name "/PC15") (class "Default")
      (node (ref "C20") (pin "2") (pintype "passive"))
      (node (ref "IC") (pin "4") (pinfunction "PC15/OSC32_4") (pintype "passive"))
      (node (ref "Y2") (pin "2") (pinfunction "OSC2_2") (pintype "passive"))
    )
    (net (code "64") (name "/PD0") (class "Default")
      (node (ref "C17") (pin "2") (pinfunction "2_2") (pintype "passive"))
      (node (ref "IC") (pin "5") (pinfunction "PD0/OSCIN_5") (pintype "passive"))
      (node (ref "Y1") (pin "3") (pinfunction "HOT_3") (pintype "passive"))
    )
    (net (code "65") (name "/PD1") (class "Default")
      (node (ref "C18") (pin "2") (pinfunction "2_2") (pintype "passive"))
      (node (ref "IC") (pin "6") (pinfunction "PD1/OSCOUT_6") (pintype "passive"))
      (node (ref "Y1") (pin "1") (pinfunction "HOT_1") (pintype "passive"))
    )
    (net (code "66") (name "/PD2") (class "Default")
      (node (ref "IC") (pin "54") (pinfunction "PD2/TIM3_ETR/U5_RX/SDIO_CMD_54") (pintype "passive"))
    )
    (net (code "67") (name "/RESET") (class "Default")
      (node (ref "C21") (pin "2") (pintype "passive"))
      (node (ref "IC") (pin "7") (pinfunction "NRST_7") (pintype "passive"))
      (node (ref "R30") (pin "2") (pintype "passive"))
      (node (ref "RST") (pin "1") (pinfunction "1_1") (pintype "passive"))
    )
    (net (code "68") (name "/VCC3.3A") (class "Default")
      (node (ref "C22") (pin "2") (pintype "passive"))
      (node (ref "C23") (pin "2") (pintype "passive"))
      (node (ref "IC") (pin "13") (pinfunction "VDDA_13") (pintype "passive"))
      (node (ref "R31") (pin "2") (pintype "passive"))
    )
    (net (code "69") (name "DGND") (class "Default")
      (node (ref "C15") (pin "1") (pinfunction "1_1") (pintype "passive"))
      (node (ref "C17") (pin "1") (pinfunction "1_1") (pintype "passive"))
      (node (ref "C18") (pin "1") (pinfunction "1_1") (pintype "passive"))
      (node (ref "C19") (pin "1") (pintype "passive"))
      (node (ref "C20") (pin "1") (pintype "passive"))
      (node (ref "C21") (pin "1") (pintype "passive"))
      (node (ref "C22") (pin "1") (pintype "passive"))
      (node (ref "C23") (pin "1") (pintype "passive"))
      (node (ref "C24") (pin "1") (pintype "passive"))
      (node (ref "C25") (pin "1") (pintype "passive"))
      (node (ref "C26") (pin "1") (pintype "passive"))
      (node (ref "C27") (pin "1") (pintype "passive"))
      (node (ref "C60") (pin "2") (pinfunction "2_2") (pintype "passive"))
      (node (ref "C61") (pin "2") (pinfunction "K_2") (pintype "passive"))
      (node (ref "C62") (pin "2") (pinfunction "2_2") (pintype "passive"))
      (node (ref "C68") (pin "2") (pinfunction "2_2") (pintype "passive"))
      (node (ref "C69") (pin "2") (pinfunction "2_2") (pintype "passive"))
      (node (ref "C75") (pin "2") (pinfunction "2_2") (pintype "passive"))
      (node (ref "C76") (pin "2") (pinfunction "2_2") (pintype "passive"))
      (node (ref "C77") (pin "2") (pinfunction "2_2") (pintype "passive"))
      (node (ref "C78") (pin "2") (pinfunction "2_2") (pintype "passive"))
      (node (ref "C79") (pin "2") (pinfunction "2_2") (pintype "passive"))
      (node (ref "C80") (pin "2") (pinfunction "2_2") (pintype "passive"))
      (node (ref "C88") (pin "2") (pinfunction "K_2") (pintype "passive"))
      (node (ref "CN2") (pin "4") (pinfunction "4_4") (pintype "passive"))
      (node (ref "DBG") (pin "1") (pinfunction "1_1") (pintype "passive"))
      (node (ref "DBG") (pin "4") (pinfunction "4_4") (pintype "passive"))
      (node (ref "IC") (pin "12") (pinfunction "VSSA_12") (pintype "passive"))
      (node (ref "IC") (pin "18") (pinfunction "VSS_18") (pintype "passive"))
      (node (ref "IC") (pin "31") (pinfunction "VSS_31") (pintype "passive"))
      (node (ref "IC") (pin "47") (pinfunction "VSS_47") (pintype "passive"))
      (node (ref "IC") (pin "63") (pinfunction "VSS_63") (pintype "passive"))
      (node (ref "OLED") (pin "1") (pinfunction "1_1") (pintype "passive"))
      (node (ref "R32") (pin "2") (pintype "passive"))
      (node (ref "RST") (pin "2") (pinfunction "2_2") (pintype "passive"))
      (node (ref "U12") (pin "2") (pinfunction "GND_2") (pintype "passive"))
      (node (ref "U2") (pin "15") (pinfunction "VSS_15") (pintype "passive"))
      (node (ref "U5") (pin "15") (pinfunction "VSS_15") (pintype "passive"))
      (node (ref "U8") (pin "15") (pinfunction "VSS_15") (pintype "passive"))
      (node (ref "USB") (pin "5") (pinfunction "GND_5") (pintype "passive"))
      (node (ref "Y1") (pin "2") (pinfunction "GND_2") (pintype "passive"))
      (node (ref "Y1") (pin "4") (pinfunction "GND_4") (pintype "passive"))
    )
    (net (code "70") (name "GND") (class "Default")
      (node (ref "C13") (pin "2") (pintype "passive"))
      (node (ref "C14") (pin "1") (pintype "passive"))
      (node (ref "C16") (pin "1") (pintype "passive"))
      (node (ref "C4") (pin "1") (pinfunction "1_1") (pintype "passive"))
      (node (ref "C5") (pin "1") (pinfunction "1_1") (pintype "passive"))
      (node (ref "C56") (pin "2") (pinfunction "K_2") (pintype "passive"))
      (node (ref "C57") (pin "2") (pinfunction "2_2") (pintype "passive"))
      (node (ref "C58") (pin "2") (pinfunction "2_2") (pintype "passive"))
      (node (ref "C6") (pin "1") (pinfunction "1_1") (pintype "passive"))
      (node (ref "C63") (pin "2") (pinfunction "2_2") (pintype "passive"))
      (node (ref "C64") (pin "2") (pinfunction "2_2") (pintype "passive"))
      (node (ref "CN1") (pin "4") (pinfunction "4_4") (pintype "passive"))
      (node (ref "DC_IN") (pin "2") (pintype "power_in"))
      (node (ref "DC_IN") (pin "3") (pintype "power_in"))
      (node (ref "R18") (pin "1") (pintype "passive"))
      (node (ref "R22") (pin "1") (pintype "passive"))
      (node (ref "R26") (pin "1") (pintype "passive"))
      (node (ref "R29") (pin "2") (pintype "passive"))
      (node (ref "R3") (pin "1") (pinfunction "1_1") (pintype "passive"))
      (node (ref "R52") (pin "2") (pinfunction "2_2") (pintype "passive"))
      (node (ref "R6") (pin "1") (pinfunction "1_1") (pintype "passive"))
      (node (ref "R9") (pin "1") (pinfunction "1_1") (pintype "passive"))
      (node (ref "U1") (pin "11") (pinfunction "VSS_11") (pintype "passive"))
      (node (ref "U13") (pin "1") (pinfunction "GND_1") (pintype "passive"))
      (node (ref "U2") (pin "2") (pinfunction "COM_2") (pintype "passive"))
      (node (ref "U5") (pin "2") (pinfunction "COM_2") (pintype "passive"))
      (node (ref "U8") (pin "2") (pinfunction "COM_2") (pintype "passive"))
    )
    (net (code "71") (name "Net-(C10-Pad1)") (class "Default")
      (node (ref "C10") (pin "1") (pintype "passive"))
      (node (ref "R16") (pin "2") (pintype "passive"))
      (node (ref "R17") (pin "1") (pintype "passive"))
    )
    (net (code "72") (name "Net-(C10-Pad2)") (class "Default")
      (node (ref "C10") (pin "2") (pintype "passive"))
      (node (ref "R18") (pin "2") (pintype "passive"))
      (node (ref "R19") (pin "1") (pintype "passive"))
    )
    (net (code "73") (name "Net-(C11-Pad1)") (class "Default")
      (node (ref "C11") (pin "1") (pintype "passive"))
      (node (ref "R20") (pin "2") (pintype "passive"))
      (node (ref "R21") (pin "1") (pintype "passive"))
    )
    (net (code "74") (name "Net-(C11-Pad2)") (class "Default")
      (node (ref "C11") (pin "2") (pintype "passive"))
      (node (ref "R22") (pin "2") (pintype "passive"))
      (node (ref "R23") (pin "1") (pintype "passive"))
    )
    (net (code "75") (name "Net-(C12-Pad1)") (class "Default")
      (node (ref "C12") (pin "1") (pintype "passive"))
      (node (ref "R24") (pin "2") (pintype "passive"))
      (node (ref "R25") (pin "1") (pintype "passive"))
    )
    (net (code "76") (name "Net-(C12-Pad2)") (class "Default")
      (node (ref "C12") (pin "2") (pintype "passive"))
      (node (ref "R26") (pin "2") (pintype "passive"))
      (node (ref "R27") (pin "1") (pintype "passive"))
    )
    (net (code "77") (name "Net-(C59-Pad1)") (class "Default")
      (node (ref "C59") (pin "1") (pinfunction "1_1") (pintype "passive"))
      (node (ref "R53") (pin "2") (pinfunction "2_2") (pintype "passive"))
    )
    (net (code "78") (name "Net-(C78-Pad1)") (class "Default")
      (node (ref "C78") (pin "1") (pinfunction "1_1") (pintype "passive"))
      (node (ref "CN2") (pin "8") (pinfunction "8_8") (pintype "passive"))
      (node (ref "R62") (pin "1") (pinfunction "1_1") (pintype "passive"))
    )
    (net (code "79") (name "Net-(C79-Pad1)") (class "Default")
      (node (ref "C79") (pin "1") (pinfunction "1_1") (pintype "passive"))
      (node (ref "CN2") (pin "7") (pinfunction "7_7") (pintype "passive"))
      (node (ref "R61") (pin "1") (pinfunction "1_1") (pintype "passive"))
    )
    (net (code "80") (name "Net-(C80-Pad1)") (class "Default")
      (node (ref "C80") (pin "1") (pinfunction "1_1") (pintype "passive"))
      (node (ref "CN2") (pin "6") (pinfunction "6_6") (pintype "passive"))
      (node (ref "R60") (pin "1") (pinfunction "1_1") (pintype "passive"))
    )
    (net (code "81") (name "Net-(CN2-Pad1)") (class "Default")
      (node (ref "CN2") (pin "1") (pinfunction "1_1") (pintype "passive"))
      (node (ref "R54") (pin "2") (pinfunction "2_2") (pintype "passive"))
      (node (ref "R57") (pin "1") (pinfunction "1_1") (pintype "passive"))
    )
    (net (code "82") (name "Net-(CN2-Pad2)") (class "Default")
      (node (ref "CN2") (pin "2") (pinfunction "2_2") (pintype "passive"))
      (node (ref "R55") (pin "2") (pinfunction "2_2") (pintype "passive"))
      (node (ref "R58") (pin "1") (pinfunction "1_1") (pintype "passive"))
    )
    (net (code "83") (name "Net-(CN2-Pad3)") (class "Default")
      (node (ref "CN2") (pin "3") (pinfunction "3_3") (pintype "passive"))
      (node (ref "R56") (pin "2") (pinfunction "2_2") (pintype "passive"))
      (node (ref "R59") (pin "1") (pinfunction "1_1") (pintype "passive"))
    )
    (net (code "84") (name "Net-(D1-K)") (class "Default")
      (node (ref "C1") (pin "2") (pinfunction "2_2") (pintype "passive"))
      (node (ref "D1") (pin "2") (pinfunction "K_2") (pintype "passive"))
      (node (ref "U2") (pin "7") (pinfunction "VB_7") (pintype "passive"))
    )
    (net (code "85") (name "Net-(D2-A)") (class "Default")
      (node (ref "D2") (pin "1") (pinfunction "A_1") (pintype "passive"))
      (node (ref "Q1") (pin "1") (pinfunction "G_1") (pintype "passive"))
      (node (ref "R1") (pin "2") (pinfunction "2_2") (pintype "passive"))
    )
    (net (code "86") (name "Net-(D2-K)") (class "Default")
      (node (ref "D2") (pin "2") (pinfunction "K_2") (pintype "passive"))
      (node (ref "R1") (pin "1") (pinfunction "1_1") (pintype "passive"))
      (node (ref "U2") (pin "8") (pinfunction "HO_8") (pintype "passive"))
    )
    (net (code "87") (name "Net-(D4-A)") (class "Default")
      (node (ref "D4") (pin "1") (pinfunction "A_1") (pintype "passive"))
      (node (ref "Q2") (pin "1") (pinfunction "G_1") (pintype "passive"))
      (node (ref "R2") (pin "2") (pinfunction "2_2") (pintype "passive"))
    )
    (net (code "88") (name "Net-(D4-K)") (class "Default")
      (node (ref "D4") (pin "2") (pinfunction "K_2") (pintype "passive"))
      (node (ref "R2") (pin "1") (pinfunction "1_1") (pintype "passive"))
      (node (ref "U2") (pin "1") (pinfunction "LO_1") (pintype "passive"))
    )
    (net (code "89") (name "Net-(D5-K)") (class "Default")
      (node (ref "C2") (pin "2") (pinfunction "2_2") (pintype "passive"))
      (node (ref "D5") (pin "2") (pinfunction "K_2") (pintype "passive"))
      (node (ref "U5") (pin "7") (pinfunction "VB_7") (pintype "passive"))
    )
    (net (code "90") (name "Net-(D6-A)") (class "Default")
      (node (ref "D6") (pin "1") (pinfunction "A_1") (pintype "passive"))
      (node (ref "Q3") (pin "1") (pinfunction "G_1") (pintype "passive"))
      (node (ref "R4") (pin "2") (pinfunction "2_2") (pintype "passive"))
    )
    (net (code "91") (name "Net-(D6-K)") (class "Default")
      (node (ref "D6") (pin "2") (pinfunction "K_2") (pintype "passive"))
      (node (ref "R4") (pin "1") (pinfunction "1_1") (pintype "passive"))
      (node (ref "U5") (pin "8") (pinfunction "HO_8") (pintype "passive"))
    )
    (net (code "92") (name "Net-(D8-A)") (class "Default")
      (node (ref "D8") (pin "1") (pinfunction "A_1") (pintype "passive"))
      (node (ref "Q4") (pin "1") (pinfunction "G_1") (pintype "passive"))
      (node (ref "R5") (pin "2") (pinfunction "2_2") (pintype "passive"))
    )
    (net (code "93") (name "Net-(D8-K)") (class "Default")
      (node (ref "D8") (pin "2") (pinfunction "K_2") (pintype "passive"))
      (node (ref "R5") (pin "1") (pinfunction "1_1") (pintype "passive"))
      (node (ref "U5") (pin "1") (pinfunction "LO_1") (pintype "passive"))
    )
    (net (code "94") (name "Net-(D10-K)") (class "Default")
      (node (ref "C3") (pin "2") (pinfunction "2_2") (pintype "passive"))
      (node (ref "D10") (pin "2") (pinfunction "K_2") (pintype "passive"))
      (node (ref "U8") (pin "7") (pinfunction "VB_7") (pintype "passive"))
    )
    (net (code "95") (name "Net-(D11-A)") (class "Default")
      (node (ref "D11") (pin "1") (pinfunction "A_1") (pintype "passive"))
      (node (ref "Q5") (pin "1") (pinfunction "G_1") (pintype "passive"))
      (node (ref "R7") (pin "2") (pinfunction "2_2") (pintype "passive"))
    )
    (net (code "96") (name "Net-(D11-K)") (class "Default")
      (node (ref "D11") (pin "2") (pinfunction "K_2") (pintype "passive"))
      (node (ref "R7") (pin "1") (pinfunction "1_1") (pintype "passive"))
      (node (ref "U8") (pin "8") (pinfunction "HO_8") (pintype "passive"))
    )
    (net (code "97") (name "Net-(D15-A)") (class "Default")
      (node (ref "D15") (pin "1") (pinfunction "A_1") (pintype "passive"))
      (node (ref "Q6") (pin "1") (pinfunction "G_1") (pintype "passive"))
      (node (ref "R8") (pin "2") (pinfunction "2_2") (pintype "passive"))
    )
    (net (code "98") (name "Net-(D15-K)") (class "Default")
      (node (ref "D15") (pin "2") (pinfunction "K_2") (pintype "passive"))
      (node (ref "R8") (pin "1") (pinfunction "1_1") (pintype "passive"))
      (node (ref "U8") (pin "1") (pinfunction "LO_1") (pintype "passive"))
    )
    (net (code "99") (name "Net-(U13-BST)") (class "Default")
      (node (ref "C73") (pin "1") (pinfunction "1_1") (pintype "passive"))
      (node (ref "U13") (pin "6") (pinfunction "BST_6") (pintype "passive"))
    )
    (net (code "100") (name "Net-(U13-EN)") (class "Default")
      (node (ref "R50") (pin "2") (pinfunction "2_2") (pintype "passive"))
      (node (ref "U13") (pin "5") (pinfunction "EN_5") (pintype "passive"))
    )
    (net (code "101") (name "Net-(U13-FB)") (class "Default")
      (node (ref "R51") (pin "1") (pinfunction "1_1") (pintype "passive"))
      (node (ref "R52") (pin "1") (pinfunction "1_1") (pintype "passive"))
      (node (ref "R53") (pin "1") (pinfunction "1_1") (pintype "passive"))
      (node (ref "U13") (pin "4") (pinfunction "FB_4") (pintype "passive"))
    )
    (net (code "102") (name "Net-(U13-SW)") (class "Default")
      (node (ref "C73") (pin "2") (pinfunction "2_2") (pintype "passive"))
      (node (ref "L1") (pin "1") (pinfunction "1_1") (pintype "passive"))
      (node (ref "U13") (pin "2") (pinfunction "SW_2") (pintype "passive"))
    )
    (net (code "103") (name "Net-(USB-D+)") (class "Default")
      (node (ref "R33") (pin "2") (pintype "passive"))
      (node (ref "R35") (pin "1") (pintype "passive"))
      (node (ref "USB") (pin "3") (pinfunction "D+_3") (pintype "passive"))
    )
    (net (code "104") (name "Net-(USB-D-)") (class "Default")
      (node (ref "R34") (pin "1") (pintype "passive"))
      (node (ref "USB") (pin "2") (pinfunction "D-_2") (pintype "passive"))
    )
    (net (code "105") (name "POWER") (class "Default")
      (node (ref "C4") (pin "2") (pinfunction "2_2") (pintype "passive"))
      (node (ref "C5") (pin "2") (pinfunction "2_2") (pintype "passive"))
      (node (ref "C6") (pin "2") (pinfunction "2_2") (pintype "passive"))
      (node (ref "C63") (pin "1") (pinfunction "1_1") (pintype "passive"))
      (node (ref "C64") (pin "1") (pinfunction "1_1") (pintype "passive"))
      (node (ref "CN1") (pin "5") (pinfunction "5_5") (pintype "passive"))
      (node (ref "D1") (pin "1") (pinfunction "A_1") (pintype "passive"))
      (node (ref "D10") (pin "1") (pinfunction "A_1") (pintype "passive"))
      (node (ref "D5") (pin "1") (pinfunction "A_1") (pintype "passive"))
      (node (ref "DC_IN") (pin "1") (pintype "power_in"))
      (node (ref "Q1") (pin "2") (pinfunction "D_2") (pintype "passive"))
      (node (ref "Q3") (pin "2") (pinfunction "D_2") (pintype "passive"))
      (node (ref "Q5") (pin "2") (pinfunction "D_2") (pintype "passive"))
      (node (ref "R50") (pin "1") (pinfunction "1_1") (pintype "passive"))
      (node (ref "U13") (pin "3") (pinfunction "VIN_3") (pintype "passive"))
      (node (ref "U2") (pin "3") (pinfunction "VCC_3") (pintype "passive"))
      (node (ref "U5") (pin "3") (pinfunction "VCC_3") (pintype "passive"))
      (node (ref "U8") (pin "3") (pinfunction "VCC_3") (pintype "passive"))
    )
    (net (code "106") (name "VCC3.3") (class "Default")
      (node (ref "C14") (pin "2") (pintype "passive"))
      (node (ref "C15") (pin "2") (pinfunction "2_2") (pintype "passive"))
      (node (ref "C16") (pin "2") (pintype "passive"))
      (node (ref "C24") (pin "2") (pintype "passive"))
      (node (ref "C25") (pin "2") (pintype "passive"))
      (node (ref "C26") (pin "2") (pintype "passive"))
      (node (ref "C27") (pin "2") (pintype "passive"))
      (node (ref "C61") (pin "1") (pinfunction "A_1") (pintype "passive"))
      (node (ref "C62") (pin "1") (pinfunction "1_1") (pintype "passive"))
      (node (ref "C69") (pin "1") (pinfunction "1_1") (pintype "passive"))
      (node (ref "D19") (pin "2") (pinfunction "K_2") (pintype "passive"))
      (node (ref "D20") (pin "2") (pinfunction "K_2") (pintype "passive"))
      (node (ref "D21") (pin "2") (pinfunction "K_2") (pintype "passive"))
      (node (ref "DBG") (pin "5") (pinfunction "5_5") (pintype "passive"))
      (node (ref "IC") (pin "1") (pinfunction "VBAT_1") (pintype "passive"))
      (node (ref "IC") (pin "19") (pinfunction "VDD_19") (pintype "passive"))
      (node (ref "IC") (pin "32") (pinfunction "VDD_32") (pintype "passive"))
      (node (ref "IC") (pin "48") (pinfunction "VDD_48") (pintype "passive"))
      (node (ref "IC") (pin "64") (pinfunction "VDD_64") (pintype "passive"))
      (node (ref "R28") (pin "1") (pintype "passive"))
      (node (ref "R30") (pin "1") (pintype "passive"))
      (node (ref "R31") (pin "1") (pintype "passive"))
      (node (ref "R33") (pin "1") (pintype "passive"))
      (node (ref "R54") (pin "1") (pinfunction "1_1") (pintype "passive"))
      (node (ref "R55") (pin "1") (pinfunction "1_1") (pintype "passive"))
      (node (ref "R56") (pin "1") (pinfunction "1_1") (pintype "passive"))
      (node (ref "U1") (pin "4") (pinfunction "VDD_4") (pintype "passive"))
      (node (ref "U12") (pin "5") (pinfunction "OUT_5") (pintype "passive"))
    )
    (net (code "107") (name "VCC5") (class "Default")
      (node (ref "C56") (pin "1") (pinfunction "A_1") (pintype "passive"))
      (node (ref "C57") (pin "1") (pinfunction "1_1") (pintype "passive"))
      (node (ref "C58") (pin "1") (pinfunction "1_1") (pintype "passive"))
      (node (ref "C59") (pin "2") (pinfunction "2_2") (pintype "passive"))
      (node (ref "C60") (pin "1") (pinfunction "1_1") (pintype "passive"))
      (node (ref "C68") (pin "1") (pinfunction "1_1") (pintype "passive"))
      (node (ref "C88") (pin "1") (pinfunction "A_1") (pintype "passive"))
      (node (ref "CN2") (pin "5") (pinfunction "5_5") (pintype "passive"))
      (node (ref "DBG") (pin "6") (pinfunction "6_6") (pintype "passive"))
      (node (ref "L1") (pin "2") (pinfunction "2_2") (pintype "passive"))
      (node (ref "OLED") (pin "2") (pinfunction "2_2") (pintype "passive"))
      (node (ref "R51") (pin "2") (pinfunction "2_2") (pintype "passive"))
      (node (ref "U12") (pin "1") (pinfunction "VIN_1") (pintype "passive"))
      (node (ref "U12") (pin "3") (pinfunction "EN_3") (pintype "passive"))
      (node (ref "U2") (pin "11") (pinfunction "VDD_11") (pintype "passive"))
      (node (ref "U5") (pin "11") (pinfunction "VDD_11") (pintype "passive"))
      (node (ref "U8") (pin "11") (pinfunction "VDD_11") (pintype "passive"))
    )
    (net (code "108") (name "VUSB") (class "Default")
      (node (ref "USB") (pin "1") (pinfunction "VCC_1") (pintype "passive"))
    )
    (net (code "109") (name "unconnected-(U2-NC-Pad4)") (class "Default")
      (node (ref "U2") (pin "4") (pinfunction "NC_4") (pintype "passive+no_connect"))
    )
    (net (code "110") (name "unconnected-(U2-NC-Pad5)") (class "Default")
      (node (ref "U2") (pin "5") (pinfunction "NC_5") (pintype "passive+no_connect"))
    )
    (net (code "111") (name "unconnected-(U2-NC-Pad9)") (class "Default")
      (node (ref "U2") (pin "9") (pinfunction "NC_9") (pintype "passive+no_connect"))
    )
    (net (code "112") (name "unconnected-(U2-NC-Pad10)") (class "Default")
      (node (ref "U2") (pin "10") (pinfunction "NC_10") (pintype "passive+no_connect"))
    )
    (net (code "113") (name "unconnected-(U2-NC-Pad16)") (class "Default")
      (node (ref "U2") (pin "16") (pinfunction "NC_16") (pintype "passive+no_connect"))
    )
    (net (code "114") (name "unconnected-(U5-NC-Pad4)") (class "Default")
      (node (ref "U5") (pin "4") (pinfunction "NC_4") (pintype "passive+no_connect"))
    )
    (net (code "115") (name "unconnected-(U5-NC-Pad5)") (class "Default")
      (node (ref "U5") (pin "5") (pinfunction "NC_5") (pintype "passive+no_connect"))
    )
    (net (code "116") (name "unconnected-(U5-NC-Pad9)") (class "Default")
      (node (ref "U5") (pin "9") (pinfunction "NC_9") (pintype "passive+no_connect"))
    )
    (net (code "117") (name "unconnected-(U5-NC-Pad10)") (class "Default")
      (node (ref "U5") (pin "10") (pinfunction "NC_10") (pintype "passive+no_connect"))
    )
    (net (code "118") (name "unconnected-(U5-NC-Pad16)") (class "Default")
      (node (ref "U5") (pin "16") (pinfunction "NC_16") (pintype "passive+no_connect"))
    )
    (net (code "119") (name "unconnected-(U8-NC-Pad4)") (class "Default")
      (node (ref "U8") (pin "4") (pinfunction "NC_4") (pintype "passive+no_connect"))
    )
    (net (code "120") (name "unconnected-(U8-NC-Pad5)") (class "Default")
      (node (ref "U8") (pin "5") (pinfunction "NC_5") (pintype "passive+no_connect"))
    )
    (net (code "121") (name "unconnected-(U8-NC-Pad9)") (class "Default")
      (node (ref "U8") (pin "9") (pinfunction "NC_9") (pintype "passive+no_connect"))
    )
    (net (code "122") (name "unconnected-(U8-NC-Pad10)") (class "Default")
      (node (ref "U8") (pin "10") (pinfunction "NC_10") (pintype "passive+no_connect"))
    )
    (net (code "123") (name "unconnected-(U8-NC-Pad16)") (class "Default")
      (node (ref "U8") (pin "16") (pinfunction "NC_16") (pintype "passive+no_connect"))
    )
    (net (code "124") (name "unconnected-(U12-BP-Pad4)") (class "Default")
      (node (ref "U12") (pin "4") (pinfunction "BP_4") (pintype "passive+no_connect"))
    )
    (net (code "125") (name "unconnected-(USB-ID-Pad4)") (class "Default")
      (node (ref "USB") (pin "4") (pinfunction "ID_4") (pintype "passive"))
    )
    (net (code "126") (name "unconnected-(USB-Shell1-Pad6)") (class "Default")
      (node (ref "USB") (pin "6") (pinfunction "Shell1_6") (pintype "passive"))
    )
    (net (code "127") (name "unconnected-(USB-Shell2-Pad7)") (class "Default")
      (node (ref "USB") (pin "7") (pinfunction "Shell2_7") (pintype "passive"))
    )
    (net (code "128") (name "unconnected-(USB-Shell3-Pad8)") (class "Default")
      (node (ref "USB") (pin "8") (pinfunction "Shell3_8") (pintype "passive"))
    )
    (net (code "129") (name "unconnected-(USB-Shell4-Pad9)") (class "Default")
      (node (ref "USB") (pin "9") (pinfunction "Shell4_9") (pintype "passive"))
    )
  )
)
